# Multiplexer_Bank.net
KiCad netlist of a schematic drawn in Altium Designer
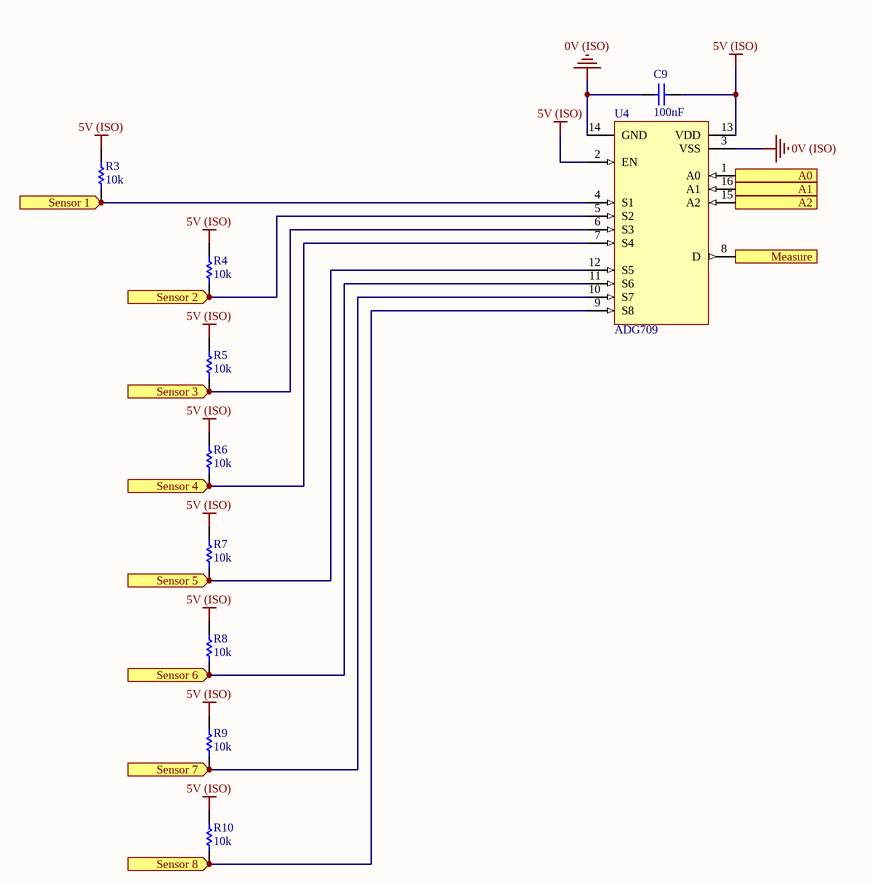
[diagram p0: Multiplexer Bank.SchDoc]

(export (version "E")
  (design (tool "Eeschema 10.0.6"))
  (components
    (comp (ref "C9")
      (value "100nF")
      (footprint "0805")
      (fields
        (field (name "ALTIUM_VALUE") "100nF")
        (field (name "TOLERANCE") "10%")
        (field (name "MATERIAL") "X7R")
        (field (name "RATED VOLTAGE") "25V")
        (field (name "PART NUMBER") "GCM21BR71E104KA37L")
        (field (name "MANUFACTURER") "muRata")
      )
      (libsource (lib "ts_19-standard-library") (part "Capacitor"))
    )
    (comp (ref "R3")
      (value "10k")
      (footprint "0805")
      (fields
        (field (name "MANUFACTURER") "YAGEO")
        (field (name "PART NUMBER") "RC0805FR0710KL")
        (field (name "TOLERANCE") "0.01")
      )
      (libsource (lib "ts_19-standard-library") (part "Resistor"))
    )
    (comp (ref "R4")
      (value "10k")
      (footprint "0805")
      (fields
        (field (name "MANUFACTURER") "YAGEO")
        (field (name "PART NUMBER") "RC0805FR0710KL")
        (field (name "TOLERANCE") "0.01")
      )
      (libsource (lib "ts_19-standard-library") (part "Resistor"))
    )
    (comp (ref "R5")
      (value "10k")
      (footprint "0805")
      (fields
        (field (name "MANUFACTURER") "YAGEO")
        (field (name "PART NUMBER") "RC0805FR0710KL")
        (field (name "TOLERANCE") "0.01")
      )
      (libsource (lib "ts_19-standard-library") (part "Resistor"))
    )
    (comp (ref "R6")
      (value "10k")
      (footprint "0805")
      (fields
        (field (name "MANUFACTURER") "YAGEO")
        (field (name "PART NUMBER") "RC0805FR0710KL")
        (field (name "TOLERANCE") "0.01")
      )
      (libsource (lib "ts_19-standard-library") (part "Resistor"))
    )
    (comp (ref "R7")
      (value "10k")
      (footprint "0805")
      (fields
        (field (name "MANUFACTURER") "YAGEO")
        (field (name "PART NUMBER") "RC0805FR0710KL")
        (field (name "TOLERANCE") "0.01")
      )
      (libsource (lib "ts_19-standard-library") (part "Resistor"))
    )
    (comp (ref "R8")
      (value "10k")
      (footprint "0805")
      (fields
        (field (name "MANUFACTURER") "YAGEO")
        (field (name "PART NUMBER") "RC0805FR0710KL")
        (field (name "TOLERANCE") "0.01")
      )
      (libsource (lib "ts_19-standard-library") (part "Resistor"))
    )
    (comp (ref "R9")
      (value "10k")
      (footprint "0805")
      (fields
        (field (name "MANUFACTURER") "YAGEO")
        (field (name "PART NUMBER") "RC0805FR0710KL")
        (field (name "TOLERANCE") "0.01")
      )
      (libsource (lib "ts_19-standard-library") (part "Resistor"))
    )
    (comp (ref "R10")
      (value "10k")
      (footprint "0805")
      (fields
        (field (name "MANUFACTURER") "YAGEO")
        (field (name "PART NUMBER") "RC0805FR0710KL")
        (field (name "TOLERANCE") "0.01")
      )
      (libsource (lib "ts_19-standard-library") (part "Resistor"))
    )
    (comp (ref "U4")
      (value "ADG709")
      (footprint "surface:AD 16-TSSOP")
      (description "2 Circuit IC Switch 4:1 4.5 Ohm 16-TSSOP")
      (fields
        (field (name "MANUFACTURER") "Analogue Devices")
        (field (name "DIGIKEY PART NUMBER") "ADG709CRUZ-REEL7TR-ND")
      )
      (libsource (lib "ts_19-standard-library") (part "ADG709"))
    )
  )
  (nets
    (net (code "1") (name "/A0") (class "Default")
      (node (ref "U4") (pin "1") (pinfunction "A0_1") (pintype "input"))
    )
    (net (code "2") (name "/A1") (class "Default")
      (node (ref "U4") (pin "16") (pinfunction "A1_16") (pintype "input"))
    )
    (net (code "3") (name "/A2") (class "Default")
      (node (ref "U4") (pin "15") (pinfunction "A2_15") (pintype "input"))
    )
    (net (code "4") (name "/Measure") (class "Default")
      (node (ref "U4") (pin "8") (pinfunction "D_8") (pintype "output"))
    )
    (net (code "5") (name "/Sensor 1") (class "Default")
      (node (ref "R3") (pin "1") (pinfunction "1_1") (pintype "passive"))
      (node (ref "U4") (pin "4") (pinfunction "S1_4") (pintype "input"))
    )
    (net (code "6") (name "/Sensor 2") (class "Default")
      (node (ref "R4") (pin "1") (pinfunction "1_1") (pintype "passive"))
      (node (ref "U4") (pin "5") (pinfunction "S2_5") (pintype "input"))
    )
    (net (code "7") (name "/Sensor 3") (class "Default")
      (node (ref "R5") (pin "1") (pinfunction "1_1") (pintype "passive"))
      (node (ref "U4") (pin "6") (pinfunction "S3_6") (pintype "input"))
    )
    (net (code "8") (name "/Sensor 4") (class "Default")
      (node (ref "R6") (pin "1") (pinfunction "1_1") (pintype "passive"))
      (node (ref "U4") (pin "7") (pinfunction "S4_7") (pintype "input"))
    )
    (net (code "9") (name "/Sensor 5") (class "Default")
      (node (ref "R7") (pin "1") (pinfunction "1_1") (pintype "passive"))
      (node (ref "U4") (pin "12") (pinfunction "S5_12") (pintype "input"))
    )
    (net (code "10") (name "/Sensor 6") (class "Default")
      (node (ref "R8") (pin "1") (pinfunction "1_1") (pintype "passive"))
      (node (ref "U4") (pin "11") (pinfunction "S6_11") (pintype "input"))
    )
    (net (code "11") (name "/Sensor 7") (class "Default")
      (node (ref "R9") (pin "1") (pinfunction "1_1") (pintype "passive"))
      (node (ref "U4") (pin "10") (pinfunction "S7_10") (pintype "input"))
    )
    (net (code "12") (name "/Sensor 8") (class "Default")
      (node (ref "R10") (pin "1") (pinfunction "1_1") (pintype "passive"))
      (node (ref "U4") (pin "9") (pinfunction "S8_9") (pintype "input"))
    )
    (net (code "13") (name "0V (ISO)") (class "Default")
      (node (ref "C9") (pin "1") (pinfunction "1_1") (pintype "passive"))
      (node (ref "U4") (pin "14") (pinfunction "GND_14") (pintype "power_in"))
      (node (ref "U4") (pin "3") (pinfunction "VSS_3") (pintype "power_in"))
    )
    (net (code "14") (name "5V (ISO)") (class "Default")
      (node (ref "C9") (pin "2") (pinfunction "2_2") (pintype "passive"))
      (node (ref "R10") (pin "2") (pinfunction "2_2") (pintype "passive"))
      (node (ref "R3") (pin "2") (pinfunction "2_2") (pintype "passive"))
      (node (ref "R4") (pin "2") (pinfunction "2_2") (pintype "passive"))
      (node (ref "R5") (pin "2") (pinfunction "2_2") (pintype "passive"))
      (node (ref "R6") (pin "2") (pinfunction "2_2") (pintype "passive"))
      (node (ref "R7") (pin "2") (pinfunction "2_2") (pintype "passive"))
      (node (ref "R8") (pin "2") (pinfunction "2_2") (pintype "passive"))
      (node (ref "R9") (pin "2") (pinfunction "2_2") (pintype "passive"))
      (node (ref "U4") (pin "13") (pinfunction "VDD_13") (pintype "power_in"))
      (node (ref "U4") (pin "2") (pinfunction "EN_2") (pintype "input"))
    )
  )
)
